# MCU.net
KiCad netlist of a schematic drawn in Altium Designer
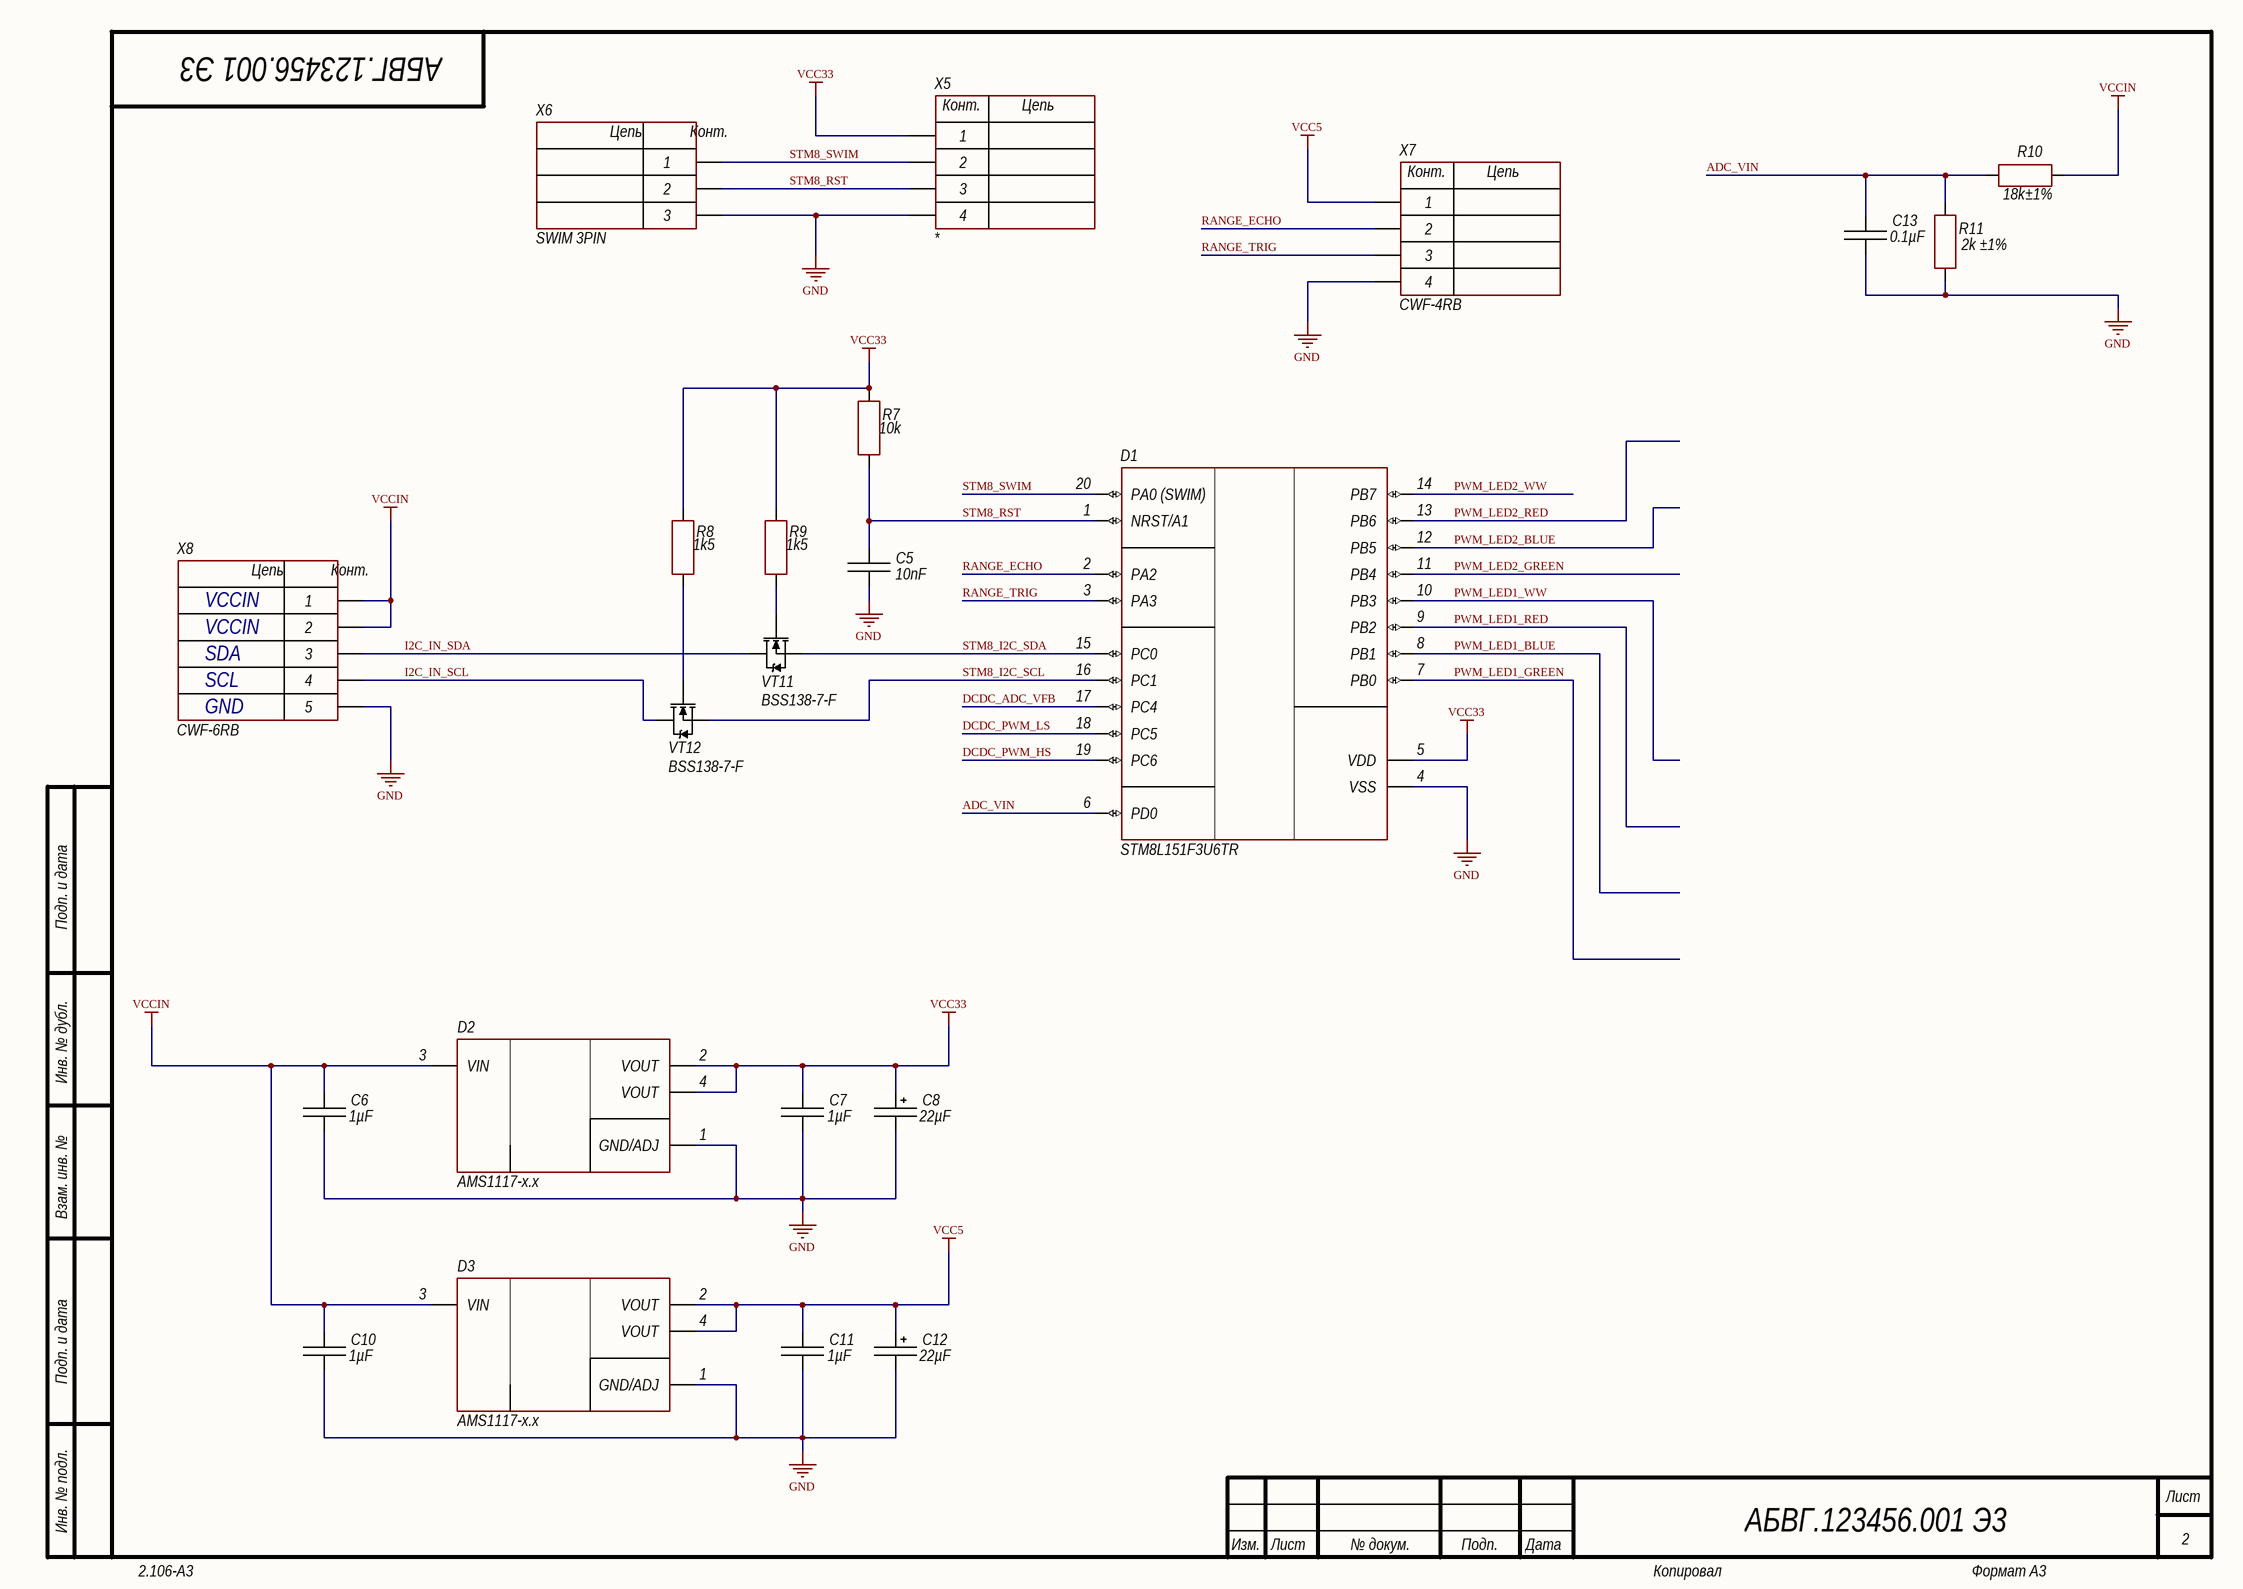
[diagram p0: MCU.SchDoc]

(export (version "E")
  (design (tool "Eeschema 10.0.6"))
  (components
    (comp (ref "C5") (value "10nF") (footprint "CH0603C") (libsource (lib "Discrete") (part "Capacitor")))
    (comp (ref "C6")
      (value "1µF")
      (footprint "CH0603C")
      (fields (field (name "MANUFACTURER") "Murata Electronics Inc."))
      (libsource (lib "Discrete") (part "Capacitor"))
    )
    (comp (ref "C7")
      (value "1µF")
      (footprint "CH0603C")
      (fields (field (name "MANUFACTURER") "Murata Electronics Inc."))
      (libsource (lib "Discrete") (part "Capacitor"))
    )
    (comp (ref "C8") (value "22µF") (footprint "TANTAL_B") (libsource (lib "Discrete") (part "TantalCap")))
    (comp (ref "C10")
      (value "1µF")
      (footprint "CH0603C")
      (fields (field (name "MANUFACTURER") "Murata Electronics Inc."))
      (libsource (lib "Discrete") (part "Capacitor"))
    )
    (comp (ref "C11")
      (value "1µF")
      (footprint "CH0603C")
      (fields (field (name "MANUFACTURER") "Murata Electronics Inc."))
      (libsource (lib "Discrete") (part "Capacitor"))
    )
    (comp (ref "C12") (value "22µF") (footprint "TANTAL_B") (libsource (lib "Discrete") (part "TantalCap")))
    (comp (ref "C13") (value "0.1µF") (footprint "CH0603C") (libsource (lib "Discrete") (part "Capacitor")))
    (comp (ref "D1")
      (value "STM8L151F3U6TR")
      (footprint "20-UFQFPN")
      (description "STM8")
      (fields (field (name "MANUFACTURER") "ST Microelectronics"))
      (libsource (lib "Digital") (part "STM8L151F3U6TR"))
    )
    (comp (ref "D2")
      (value "AMS1117-x.x")
      (footprint "SOT223")
      (description "Step-down")
      (fields (field (name "MANUFACTURER") "Advanced Monolithic Systems"))
      (libsource (lib "Power Supplies") (part "AMS1117-x.x"))
    )
    (comp (ref "D3")
      (value "AMS1117-x.x")
      (footprint "SOT223")
      (description "Step-down")
      (fields (field (name "MANUFACTURER") "Advanced Monolithic Systems"))
      (libsource (lib "Power Supplies") (part "AMS1117-x.x"))
    )
    (comp (ref "R7") (value "10k") (footprint "CH0603R") (libsource (lib "Discrete") (part "Resistor")))
    (comp (ref "R8") (value "1k5") (footprint "CH0603R") (libsource (lib "Discrete") (part "Resistor")))
    (comp (ref "R9") (value "1k5") (footprint "CH0603R") (libsource (lib "Discrete") (part "Resistor")))
    (comp (ref "R10")
      (value "18k")
      (footprint "CH0603R")
      (fields (field (name "COMPONENTKIND") "±1%"))
      (libsource (lib "") (part "Resistor_1"))
    )
    (comp (ref "R11")
      (value "2k")
      (footprint "CH0603R")
      (fields (field (name "COMPONENTKIND") "±1%"))
      (libsource (lib "Discrete") (part "Resistor"))
    )
    (comp (ref "VT11")
      (value "BSS138-7-F")
      (footprint "SOT23_132")
      (description "Mosfet")
      (fields (field (name "MANUFACTURER") "Diodes Incorporated"))
      (libsource (lib "Transistor") (part "N-chanel"))
    )
    (comp (ref "VT12")
      (value "BSS138-7-F")
      (footprint "SOT23_132")
      (description "Mosfet")
      (fields (field (name "MANUFACTURER") "Diodes Incorporated"))
      (libsource (lib "Transistor") (part "N-chanel"))
    )
    (comp (ref "X5")
      (value "*")
      (footprint "CON: CWF-4RB")
      (libsource (lib "Connectors") (part "4-Connector"))
    )
    (comp (ref "X6")
      (value "SWIM 3PIN")
      (footprint "CON: 3 PIN 1x1")
      (libsource (lib "Connectors") (part "3-Connector"))
    )
    (comp (ref "X7")
      (value "CWF-4RB")
      (footprint "CON: CWF-4RB")
      (libsource (lib "Connectors") (part "4-Connector"))
    )
    (comp (ref "X8")
      (value "CWF-6RB")
      (footprint "CON: CWF-5RB")
      (libsource (lib "Connectors") (part "5-Connector"))
    )
  )
  (nets
    (net (code "1") (name "/ADC_VIN") (class "Default")
      (node (ref "C13") (pin "1") (pinfunction "1_1") (pintype "power_in"))
      (node (ref "D1") (pin "6") (pinfunction "PD0_6") (pintype "bidirectional"))
      (node (ref "R10") (pin "1") (pinfunction "1_1") (pintype "passive"))
      (node (ref "R11") (pin "2") (pinfunction "2_2") (pintype "passive"))
    )
    (net (code "2") (name "/DCDC_ADC_VFB") (class "Default")
      (node (ref "D1") (pin "17") (pinfunction "PC4_17") (pintype "bidirectional"))
    )
    (net (code "3") (name "/DCDC_PWM_HS") (class "Default")
      (node (ref "D1") (pin "19") (pinfunction "PC6_19") (pintype "bidirectional"))
    )
    (net (code "4") (name "/DCDC_PWM_LS") (class "Default")
      (node (ref "D1") (pin "18") (pinfunction "PC5_18") (pintype "bidirectional"))
    )
    (net (code "5") (name "/I2C_IN_SCL") (class "Default")
      (node (ref "VT12") (pin "2") (pinfunction "D_2") (pintype "passive"))
      (node (ref "X8") (pin "4") (pinfunction "4_4") (pintype "power_in"))
    )
    (net (code "6") (name "/I2C_IN_SDA") (class "Default")
      (node (ref "VT11") (pin "2") (pinfunction "D_2") (pintype "passive"))
      (node (ref "X8") (pin "3") (pinfunction "3_3") (pintype "power_in"))
    )
    (net (code "7") (name "/PWM_LED1_BLUE") (class "Default")
      (node (ref "D1") (pin "8") (pinfunction "PB1_8") (pintype "bidirectional"))
    )
    (net (code "8") (name "/PWM_LED1_GREEN") (class "Default")
      (node (ref "D1") (pin "7") (pinfunction "PB0_7") (pintype "bidirectional"))
    )
    (net (code "9") (name "/PWM_LED1_RED") (class "Default")
      (node (ref "D1") (pin "9") (pinfunction "PB2_9") (pintype "bidirectional"))
    )
    (net (code "10") (name "/PWM_LED1_WW") (class "Default")
      (node (ref "D1") (pin "10") (pinfunction "PB3_10") (pintype "bidirectional"))
    )
    (net (code "11") (name "/PWM_LED2_BLUE") (class "Default")
      (node (ref "D1") (pin "12") (pinfunction "PB5_12") (pintype "bidirectional"))
    )
    (net (code "12") (name "/PWM_LED2_GREEN") (class "Default")
      (node (ref "D1") (pin "11") (pinfunction "PB4_11") (pintype "bidirectional"))
    )
    (net (code "13") (name "/PWM_LED2_RED") (class "Default")
      (node (ref "D1") (pin "13") (pinfunction "PB6_13") (pintype "bidirectional"))
    )
    (net (code "14") (name "/PWM_LED2_WW") (class "Default")
      (node (ref "D1") (pin "14") (pinfunction "PB7_14") (pintype "bidirectional"))
    )
    (net (code "15") (name "/RANGE_ECHO") (class "Default")
      (node (ref "D1") (pin "2") (pinfunction "PA2_2") (pintype "bidirectional"))
      (node (ref "X7") (pin "2") (pinfunction "2_2") (pintype "passive"))
    )
    (net (code "16") (name "/RANGE_TRIG") (class "Default")
      (node (ref "D1") (pin "3") (pinfunction "PA3_3") (pintype "bidirectional"))
      (node (ref "X7") (pin "3") (pinfunction "3_3") (pintype "power_in"))
    )
    (net (code "17") (name "/STM8_I2C_SCL") (class "Default")
      (node (ref "D1") (pin "16") (pinfunction "PC1_16") (pintype "bidirectional"))
      (node (ref "VT12") (pin "3") (pinfunction "S_3") (pintype "passive"))
    )
    (net (code "18") (name "/STM8_I2C_SDA") (class "Default")
      (node (ref "D1") (pin "15") (pinfunction "PC0_15") (pintype "bidirectional"))
      (node (ref "VT11") (pin "3") (pinfunction "S_3") (pintype "passive"))
    )
    (net (code "19") (name "/STM8_RST") (class "Default")
      (node (ref "C5") (pin "2") (pinfunction "2_2") (pintype "power_in"))
      (node (ref "D1") (pin "1") (pinfunction "NRST/A1_1") (pintype "bidirectional"))
      (node (ref "R7") (pin "1") (pinfunction "1_1") (pintype "passive"))
      (node (ref "X5") (pin "3") (pinfunction "3_3") (pintype "power_in"))
      (node (ref "X6") (pin "2") (pinfunction "2_2") (pintype "passive"))
    )
    (net (code "20") (name "/STM8_SWIM") (class "Default")
      (node (ref "D1") (pin "20") (pinfunction "PA0_(SWIM)_20") (pintype "bidirectional"))
      (node (ref "X5") (pin "2") (pinfunction "2_2") (pintype "passive"))
      (node (ref "X6") (pin "1") (pinfunction "1_1") (pintype "passive"))
    )
    (net (code "21") (name "GND") (class "Default")
      (node (ref "C10") (pin "1") (pinfunction "1_1") (pintype "power_in"))
      (node (ref "C11") (pin "1") (pinfunction "1_1") (pintype "power_in"))
      (node (ref "C12") (pin "2") (pinfunction "2_2") (pintype "power_in"))
      (node (ref "C13") (pin "2") (pinfunction "2_2") (pintype "power_in"))
      (node (ref "C5") (pin "1") (pinfunction "1_1") (pintype "power_in"))
      (node (ref "C6") (pin "1") (pinfunction "1_1") (pintype "power_in"))
      (node (ref "C7") (pin "1") (pinfunction "1_1") (pintype "power_in"))
      (node (ref "C8") (pin "2") (pinfunction "2_2") (pintype "power_in"))
      (node (ref "D1") (pin "4") (pinfunction "VSS_4") (pintype "power_in"))
      (node (ref "D2") (pin "1") (pinfunction "GND/ADJ_1") (pintype "power_in"))
      (node (ref "D3") (pin "1") (pinfunction "GND/ADJ_1") (pintype "power_in"))
      (node (ref "R11") (pin "1") (pinfunction "1_1") (pintype "passive"))
      (node (ref "X5") (pin "4") (pinfunction "4_4") (pintype "power_in"))
      (node (ref "X6") (pin "3") (pinfunction "3_3") (pintype "power_in"))
      (node (ref "X7") (pin "4") (pinfunction "4_4") (pintype "power_in"))
      (node (ref "X8") (pin "5") (pinfunction "5_5") (pintype "power_in"))
    )
    (net (code "22") (name "Net-(VT11-G)") (class "Default")
      (node (ref "R9") (pin "1") (pinfunction "1_1") (pintype "passive"))
      (node (ref "VT11") (pin "1") (pinfunction "G_1") (pintype "passive"))
    )
    (net (code "23") (name "Net-(VT12-G)") (class "Default")
      (node (ref "R8") (pin "1") (pinfunction "1_1") (pintype "passive"))
      (node (ref "VT12") (pin "1") (pinfunction "G_1") (pintype "passive"))
    )
    (net (code "24") (name "VCC5") (class "Default")
      (node (ref "C11") (pin "2") (pinfunction "2_2") (pintype "power_in"))
      (node (ref "C12") (pin "1") (pinfunction "1_1") (pintype "power_in"))
      (node (ref "D3") (pin "2") (pinfunction "VOUT_2") (pintype "power_in"))
      (node (ref "D3") (pin "4") (pinfunction "VOUT_4") (pintype "power_in"))
      (node (ref "X7") (pin "1") (pinfunction "1_1") (pintype "passive"))
    )
    (net (code "25") (name "VCC33") (class "Default")
      (node (ref "C7") (pin "2") (pinfunction "2_2") (pintype "power_in"))
      (node (ref "C8") (pin "1") (pinfunction "1_1") (pintype "power_in"))
      (node (ref "D1") (pin "5") (pinfunction "VDD_5") (pintype "power_in"))
      (node (ref "D2") (pin "2") (pinfunction "VOUT_2") (pintype "power_in"))
      (node (ref "D2") (pin "4") (pinfunction "VOUT_4") (pintype "power_in"))
      (node (ref "R7") (pin "2") (pinfunction "2_2") (pintype "passive"))
      (node (ref "R8") (pin "2") (pinfunction "2_2") (pintype "passive"))
      (node (ref "R9") (pin "2") (pinfunction "2_2") (pintype "passive"))
      (node (ref "X5") (pin "1") (pinfunction "1_1") (pintype "passive"))
    )
    (net (code "26") (name "VCCIN") (class "Default")
      (node (ref "C10") (pin "2") (pinfunction "2_2") (pintype "power_in"))
      (node (ref "C6") (pin "2") (pinfunction "2_2") (pintype "power_in"))
      (node (ref "D2") (pin "3") (pinfunction "VIN_3") (pintype "power_in"))
      (node (ref "D3") (pin "3") (pinfunction "VIN_3") (pintype "power_in"))
      (node (ref "R10") (pin "2") (pinfunction "2_2") (pintype "passive"))
      (node (ref "X8") (pin "1") (pinfunction "1_1") (pintype "passive"))
      (node (ref "X8") (pin "2") (pinfunction "2_2") (pintype "passive"))
    )
  )
)
